# 2.net
KiCad netlist of a schematic drawn in Altium Designer
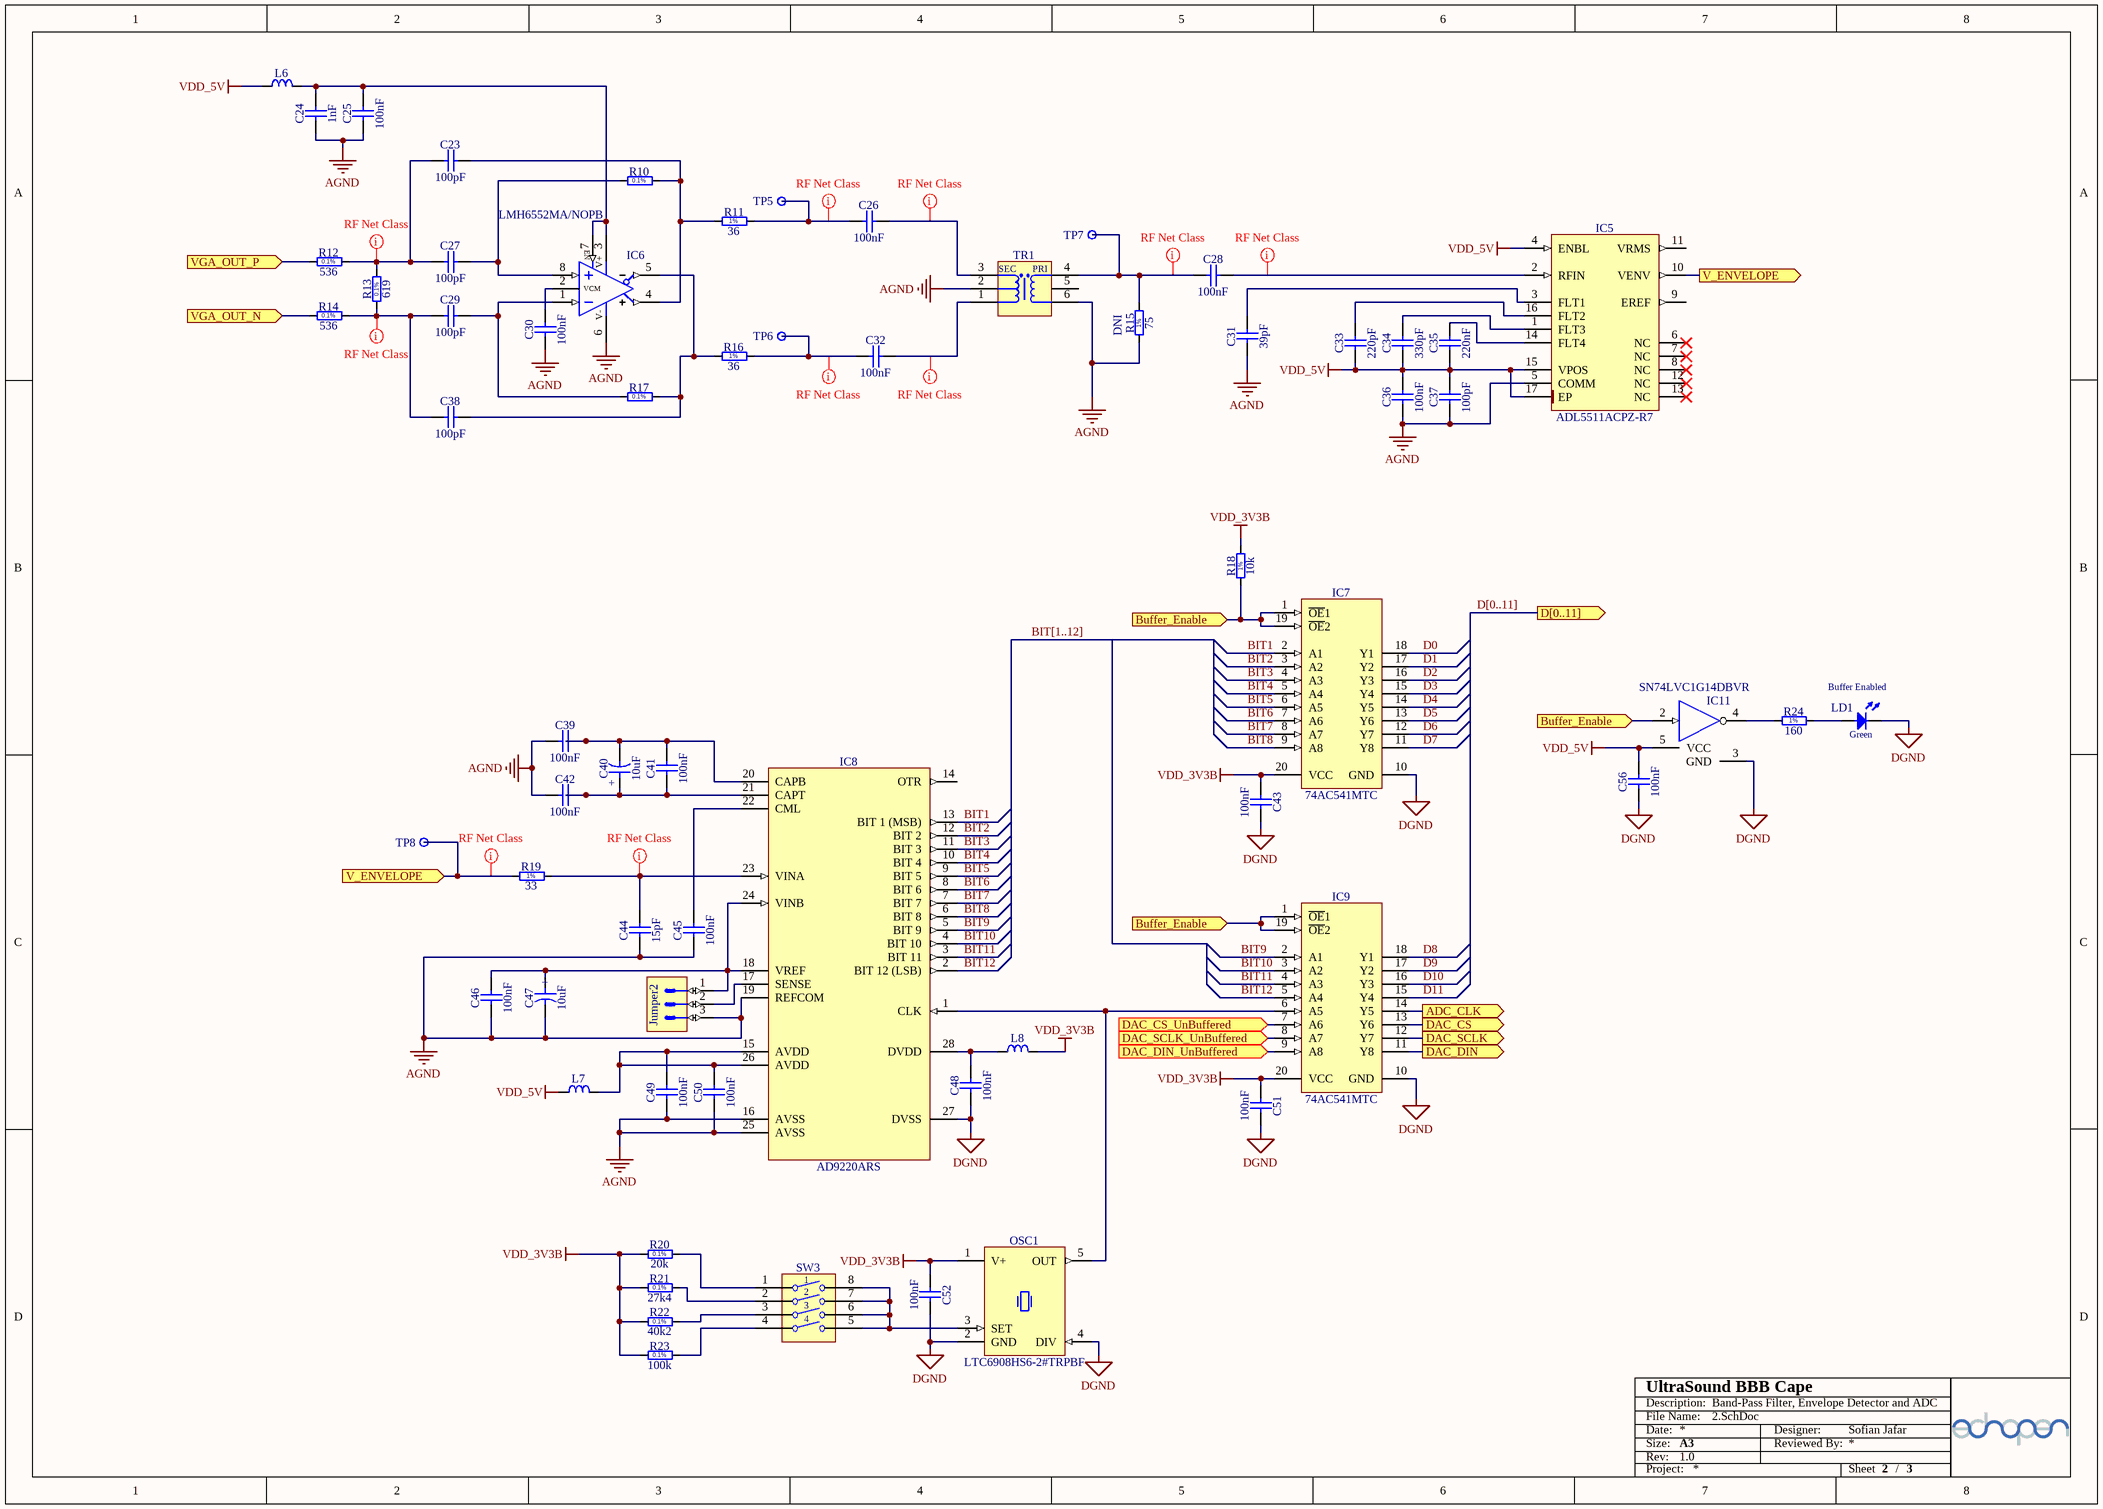
[diagram p0: 2.SchDoc]

(export (version "E")
  (design (tool "Eeschema 10.0.6"))
  (components
    (comp (ref "C23")
      (value "100pF")
      (footprint "CAPC1608X87N")
      (description "Non-polarised capacitor")
      (fields
        (field (name "PART NUMBER") "CC0603_100PF_50V_5%_NP0")
        (field (name "VOLTAGE") "50V")
        (field (name "AUTHOR") "CERN DEM JLC")
      )
      (libsource (lib "Sof-Capacitors") (part "Capacitor - non polarized"))
    )
    (comp (ref "C24")
      (value "1nF")
      (footprint "CAPC1608X87N")
      (description "Non-polarised capacitor")
      (fields
        (field (name "PART NUMBER") "CC0603_1NF_50V_10%_X7R")
        (field (name "VOLTAGE") "50V")
        (field (name "AUTHOR") "CERN DEM JLC")
      )
      (libsource (lib "Sof-Capacitors") (part "Capacitor - non polarized"))
    )
    (comp (ref "C25")
      (value "100nF")
      (footprint "CAPC1608X87N")
      (description "Non-polarised capacitor")
      (fields
        (field (name "PART NUMBER") "CC0603_100NF_50V_10%_X7R")
        (field (name "VOLTAGE") "50V")
        (field (name "AUTHOR") "CERN DEM JLC")
      )
      (libsource (lib "Sof-Capacitors") (part "Capacitor - non polarized"))
    )
    (comp (ref "C26")
      (value "100nF")
      (footprint "CAPC1608X87N")
      (description "Non-polarised capacitor")
      (fields
        (field (name "PART NUMBER") "CC0603_100NF_50V_10%_X7R")
        (field (name "VOLTAGE") "50V")
        (field (name "AUTHOR") "CERN DEM JLC")
      )
      (libsource (lib "Sof-Capacitors") (part "Capacitor - non polarized"))
    )
    (comp (ref "C27")
      (value "100pF")
      (footprint "CAPC1608X87N")
      (description "Non-polarised capacitor")
      (fields
        (field (name "PART NUMBER") "CC0603_100PF_50V_5%_NP0")
        (field (name "VOLTAGE") "50V")
        (field (name "AUTHOR") "CERN DEM JLC")
      )
      (libsource (lib "Sof-Capacitors") (part "Capacitor - non polarized"))
    )
    (comp (ref "C28")
      (value "100nF")
      (footprint "CAPC1608X87N")
      (description "Non-polarised capacitor")
      (fields
        (field (name "PART NUMBER") "CC0603_100NF_50V_10%_X7R")
        (field (name "VOLTAGE") "50V")
        (field (name "AUTHOR") "CERN DEM JLC")
      )
      (libsource (lib "Sof-Capacitors") (part "Capacitor - non polarized"))
    )
    (comp (ref "C29")
      (value "100pF")
      (footprint "CAPC1608X87N")
      (description "Non-polarised capacitor")
      (fields
        (field (name "PART NUMBER") "CC0603_100PF_50V_5%_NP0")
        (field (name "VOLTAGE") "50V")
        (field (name "AUTHOR") "CERN DEM JLC")
      )
      (libsource (lib "Sof-Capacitors") (part "Capacitor - non polarized"))
    )
    (comp (ref "C30")
      (value "100nF")
      (footprint "CAPC1608X87N")
      (description "Non-polarised capacitor")
      (fields
        (field (name "PART NUMBER") "CC0603_100NF_50V_10%_X7R")
        (field (name "VOLTAGE") "50V")
        (field (name "AUTHOR") "CERN DEM JLC")
      )
      (libsource (lib "Sof-Capacitors") (part "Capacitor - non polarized"))
    )
    (comp (ref "C31")
      (value "39pF")
      (footprint "CAPC1608X87N")
      (description "Non-polarised capacitor")
      (fields
        (field (name "PART NUMBER") "CC0603_39PF_50V_5%_NP0")
        (field (name "VOLTAGE") "50V")
        (field (name "AUTHOR") "CERN DEM JLC")
      )
      (libsource (lib "Sof-Capacitors") (part "Capacitor - non polarized"))
    )
    (comp (ref "C32")
      (value "100nF")
      (footprint "CAPC1608X87N")
      (description "Non-polarised capacitor")
      (fields
        (field (name "PART NUMBER") "CC0603_100NF_50V_10%_X7R")
        (field (name "VOLTAGE") "50V")
        (field (name "AUTHOR") "CERN DEM JLC")
      )
      (libsource (lib "Sof-Capacitors") (part "Capacitor - non polarized"))
    )
    (comp (ref "C33")
      (value "220pF")
      (footprint "CAPC1608X87N")
      (description "Non-polarised capacitor")
      (fields
        (field (name "PART NUMBER") "CC0603_220PF_50V_5%_NP0")
        (field (name "VOLTAGE") "50V")
        (field (name "AUTHOR") "CERN DEM JLC")
      )
      (libsource (lib "Sof-Capacitors") (part "Capacitor - non polarized"))
    )
    (comp (ref "C34")
      (value "330pF")
      (footprint "CAPC1608X87N")
      (description "Non-polarised capacitor")
      (fields
        (field (name "PART NUMBER") "CC0603_330PF_50V_5%_NP0")
        (field (name "VOLTAGE") "50V")
        (field (name "AUTHOR") "CERN DEM JLC")
      )
      (libsource (lib "Sof-Capacitors") (part "Capacitor - non polarized"))
    )
    (comp (ref "C35")
      (value "220nF")
      (footprint "CAPC1608X87N")
      (description "Non-polarised capacitor")
      (fields
        (field (name "PART NUMBER") "CC0603_220NF_10V_10%_X7R")
        (field (name "VOLTAGE") "10V")
        (field (name "AUTHOR") "CERN DEM JLC")
      )
      (libsource (lib "Sof-Capacitors") (part "Capacitor - non polarized"))
    )
    (comp (ref "C36")
      (value "100nF")
      (footprint "CAPC1608X87N")
      (description "Non-polarised capacitor")
      (fields
        (field (name "PART NUMBER") "CC0603_100NF_50V_10%_X7R")
        (field (name "VOLTAGE") "50V")
        (field (name "AUTHOR") "CERN DEM JLC")
      )
      (libsource (lib "Sof-Capacitors") (part "Capacitor - non polarized"))
    )
    (comp (ref "C37")
      (value "100pF")
      (footprint "CAPC1608X87N")
      (description "Non-polarised capacitor")
      (fields
        (field (name "PART NUMBER") "CC0603_100PF_50V_5%_NP0")
        (field (name "VOLTAGE") "50V")
        (field (name "AUTHOR") "CERN DEM JLC")
      )
      (libsource (lib "Sof-Capacitors") (part "Capacitor - non polarized"))
    )
    (comp (ref "C38")
      (value "100pF")
      (footprint "CAPC1608X87N")
      (description "Non-polarised capacitor")
      (fields
        (field (name "PART NUMBER") "CC0603_100PF_50V_5%_NP0")
        (field (name "VOLTAGE") "50V")
        (field (name "AUTHOR") "CERN DEM JLC")
      )
      (libsource (lib "Sof-Capacitors") (part "Capacitor - non polarized"))
    )
    (comp (ref "C39")
      (value "100nF")
      (footprint "CAPC1608X87N")
      (description "Non-polarised capacitor")
      (fields
        (field (name "PART NUMBER") "CC0603_100NF_50V_10%_X7R")
        (field (name "VOLTAGE") "50V")
        (field (name "AUTHOR") "CERN DEM JLC")
      )
      (libsource (lib "Sof-Capacitors") (part "Capacitor - non polarized"))
    )
    (comp (ref "C40")
      (value "10uF")
      (footprint "CAPMP3528X210N")
      (description "Polarised capacitor")
      (fields
        (field (name "PART NUMBER") "CTE3528-21_10UF_16V_20%_SANYO_TQC")
        (field (name "VOLTAGE") "16V")
        (field (name "AUTHOR") "CERN DEM JLC")
      )
      (libsource (lib "") (part "Capacitor - polarized_1"))
    )
    (comp (ref "C41")
      (value "100nF")
      (footprint "CAPC1608X87N")
      (description "Non-polarised capacitor")
      (fields
        (field (name "PART NUMBER") "CC0603_100NF_50V_10%_X7R")
        (field (name "VOLTAGE") "50V")
        (field (name "AUTHOR") "CERN DEM JLC")
      )
      (libsource (lib "Sof-Capacitors") (part "Capacitor - non polarized"))
    )
    (comp (ref "C42")
      (value "100nF")
      (footprint "CAPC1608X87N")
      (description "Non-polarised capacitor")
      (fields
        (field (name "PART NUMBER") "CC0603_100NF_50V_10%_X7R")
        (field (name "VOLTAGE") "50V")
        (field (name "AUTHOR") "CERN DEM JLC")
      )
      (libsource (lib "Sof-Capacitors") (part "Capacitor - non polarized"))
    )
    (comp (ref "C43")
      (value "100nF")
      (footprint "CAPC1608X87N")
      (description "Non-polarised capacitor")
      (fields
        (field (name "PART NUMBER") "CC0603_100NF_50V_10%_X7R")
        (field (name "VOLTAGE") "50V")
        (field (name "AUTHOR") "CERN DEM JLC")
      )
      (libsource (lib "Sof-Capacitors") (part "Capacitor - non polarized"))
    )
    (comp (ref "C44")
      (value "15pF")
      (footprint "CAPC1608X87N")
      (description "Non-polarised capacitor")
      (fields
        (field (name "PART NUMBER") "CC0603_15PF_50V_5%_NP0")
        (field (name "VOLTAGE") "50V")
        (field (name "AUTHOR") "CERN DEM JLC")
      )
      (libsource (lib "Sof-Capacitors") (part "Capacitor - non polarized"))
    )
    (comp (ref "C45")
      (value "100nF")
      (footprint "CAPC1608X87N")
      (description "Non-polarised capacitor")
      (fields
        (field (name "PART NUMBER") "CC0603_100NF_50V_10%_X7R")
        (field (name "VOLTAGE") "50V")
        (field (name "AUTHOR") "CERN DEM JLC")
      )
      (libsource (lib "Sof-Capacitors") (part "Capacitor - non polarized"))
    )
    (comp (ref "C46")
      (value "100nF")
      (footprint "CAPC1608X87N")
      (description "Non-polarised capacitor")
      (fields
        (field (name "PART NUMBER") "CC0603_100NF_50V_10%_X7R")
        (field (name "VOLTAGE") "50V")
        (field (name "AUTHOR") "CERN DEM JLC")
      )
      (libsource (lib "Sof-Capacitors") (part "Capacitor - non polarized"))
    )
    (comp (ref "C47")
      (value "10uF")
      (footprint "CAPMP3528X210N")
      (description "Polarised capacitor")
      (fields
        (field (name "PART NUMBER") "CTE3528-21_10UF_16V_20%_SANYO_TQC")
        (field (name "VOLTAGE") "16V")
        (field (name "AUTHOR") "CERN DEM JLC")
      )
      (libsource (lib "Sof-Capacitors") (part "Capacitor - polarized"))
    )
    (comp (ref "C48")
      (value "100nF")
      (footprint "CAPC1608X87N")
      (description "Non-polarised capacitor")
      (fields
        (field (name "PART NUMBER") "CC0603_100NF_50V_10%_X7R")
        (field (name "VOLTAGE") "50V")
        (field (name "AUTHOR") "CERN DEM JLC")
      )
      (libsource (lib "Sof-Capacitors") (part "Capacitor - non polarized"))
    )
    (comp (ref "C49")
      (value "100nF")
      (footprint "CAPC1608X87N")
      (description "Non-polarised capacitor")
      (fields
        (field (name "PART NUMBER") "CC0603_100NF_50V_10%_X7R")
        (field (name "VOLTAGE") "50V")
        (field (name "AUTHOR") "CERN DEM JLC")
      )
      (libsource (lib "Sof-Capacitors") (part "Capacitor - non polarized"))
    )
    (comp (ref "C50")
      (value "100nF")
      (footprint "CAPC1608X87N")
      (description "Non-polarised capacitor")
      (fields
        (field (name "PART NUMBER") "CC0603_100NF_50V_10%_X7R")
        (field (name "VOLTAGE") "50V")
        (field (name "AUTHOR") "CERN DEM JLC")
      )
      (libsource (lib "Sof-Capacitors") (part "Capacitor - non polarized"))
    )
    (comp (ref "C51")
      (value "100nF")
      (footprint "CAPC1608X87N")
      (description "Non-polarised capacitor")
      (fields
        (field (name "PART NUMBER") "CC0603_100NF_50V_10%_X7R")
        (field (name "VOLTAGE") "50V")
        (field (name "AUTHOR") "CERN DEM JLC")
      )
      (libsource (lib "Sof-Capacitors") (part "Capacitor - non polarized"))
    )
    (comp (ref "C52")
      (value "100nF")
      (footprint "CAPC1608X87N")
      (description "Non-polarised capacitor")
      (fields
        (field (name "PART NUMBER") "CC0603_100NF_50V_10%_X7R")
        (field (name "VOLTAGE") "50V")
        (field (name "AUTHOR") "CERN DEM JLC")
      )
      (libsource (lib "Sof-Capacitors") (part "Capacitor - non polarized"))
    )
    (comp (ref "C56")
      (value "100nF")
      (footprint "CAPC1608X87N")
      (description "Non-polarised capacitor")
      (fields
        (field (name "PART NUMBER") "CC0603_100NF_50V_10%_X7R")
        (field (name "VOLTAGE") "50V")
        (field (name "AUTHOR") "CERN DEM JLC")
      )
      (libsource (lib "Sof-Capacitors") (part "Capacitor - non polarized"))
    )
    (comp (ref "IC5")
      (value "ADL5511ACPZ-R7")
      (footprint "QFN50P300X300X80-17N-S175")
      (description "DC to 6 GHz Envelope and TruPwr RMS Detector")
      (fields (field (name "MANUFACTURER") "ANALOG DEVICES") (field (name "AUTHOR") "CERN DEM JLC"))
      (libsource (lib "Sof-ICs And Semiconductors") (part "ADL5511"))
    )
    (comp (ref "IC6")
      (value "LMH6552MA/NOPB")
      (footprint "SOIC127P600X175-8N")
      (description "1.5 GHz Fully Differential Amplifier")
      (fields (field (name "MANUFACTURER") "TEXAS INSTRUMENTS") (field (name "AUTHOR") "CERN DEM JLC"))
      (libsource (lib "Sof-ICs And Semiconductors") (part "LMH6552MA"))
    )
    (comp (ref "IC7")
      (value "74AC541MTC")
      (footprint "SOP65P640X120-20N")
      (description "Octal Buffer/Line Driver with 3-State Outputs")
      (fields (field (name "MANUFACTURER") "FAIRCHILD") (field (name "AUTHOR") "CERN DEM JLC"))
      (libsource (lib "Sof-ICs And Semiconductors") (part "74541"))
    )
    (comp (ref "IC8")
      (value "AD9220ARS")
      (footprint "SOP65P780X200-28N")
      (description "12-Bit, 10MSPS Sampling Analog-To-Digital Converter")
      (fields (field (name "MANUFACTURER") "ANALOG DEVICES") (field (name "AUTHOR") "S. Jafar"))
      (libsource (lib "Sof-ICs And Semiconductors") (part "AD9220"))
    )
    (comp (ref "IC9")
      (value "74AC541MTC")
      (footprint "SOP65P640X120-20N")
      (description "Octal Buffer/Line Driver with 3-State Outputs")
      (fields (field (name "MANUFACTURER") "FAIRCHILD") (field (name "AUTHOR") "CERN DEM JLC"))
      (libsource (lib "Sof-ICs And Semiconductors") (part "74541"))
    )
    (comp (ref "IC11")
      (value "SN74LVC1G14DBVR")
      (footprint "SOT95P280X145-5N")
      (description "Single Schmitt-Trigger Inverter")
      (fields (field (name "MANUFACTURER") "TEXAS INSTRUMENTS") (field (name "AUTHOR") "CERN DEM JLC"))
      (libsource (lib "Sof-ICs And Semiconductors") (part "741G14"))
    )
    (comp (ref "Jumper2")
      (value "~")
      (footprint "SULLINS_GRPB031VWVN")
      (description "Connector 3 Male")
      (fields
        (field (name "PART NUMBER") "SULLINS_GRPB031VWVN")
        (field (name "MANUFACTURER") "SULLINS")
        (field (name "AUTHOR") "S. Jafar")
      )
      (libsource (lib "Sof-Connectors") (part "Connector 3 Male"))
    )
    (comp (ref "L6")
      (value "75R@100MHz")
      (footprint "INDC2012X105N")
      (description "Inductor")
      (fields
        (field (name "PART NUMBER") "IND0805_MURATA_BLM21BB750SN1D")
        (field (name "POWER") "700mA")
        (field (name "AUTHOR") "S. Jafar")
      )
      (libsource (lib "Sof-Inductors & Transformers") (part "Inductor"))
    )
    (comp (ref "L7")
      (value "75R@100MHz")
      (footprint "INDC2012X105N")
      (description "Inductor")
      (fields
        (field (name "PART NUMBER") "IND0805_MURATA_BLM21BB750SN1D")
        (field (name "POWER") "700mA")
        (field (name "AUTHOR") "S. Jafar")
      )
      (libsource (lib "Sof-Inductors & Transformers") (part "Inductor"))
    )
    (comp (ref "L8")
      (value "75R@100MHz")
      (footprint "INDC2012X105N")
      (description "Inductor")
      (fields
        (field (name "PART NUMBER") "IND0805_MURATA_BLM21BB750SN1D")
        (field (name "POWER") "700mA")
        (field (name "AUTHOR") "S. Jafar")
      )
      (libsource (lib "Sof-Inductors & Transformers") (part "Inductor"))
    )
    (comp (ref "LD1")
      (value "Green")
      (footprint "LED_OSRAM_LGL29K")
      (description "LED Green 1C 2A")
      (fields
        (field (name "PART NUMBER") "LED_OSRAM_LG L29K-G2J1-24-Z")
        (field (name "MANUFACTURER") "OSRAM")
        (field (name "AUTHOR") "CERN DEM JLC")
      )
      (libsource (lib "Sof-ICs And Semiconductors") (part "LED Green 1C 2A"))
    )
    (comp (ref "OSC1")
      (value "LTC6908HS6-2#TRPBF")
      (footprint "SOT95P280X100-6N")
      (description "Resistor Set SOT-23 Oscillator 1kHz-20MHz")
      (fields
        (field (name "PART NUMBER") "LTC6900CS5")
        (field (name "MANUFACTURER") "LINEAR TECHNOLOGY")
        (field (name "AUTHOR") "S.Jafar")
      )
      (libsource (lib "Sof-ICs And Semiconductors") (part "LTC6900CS5"))
    )
    (comp (ref "R10")
      (value "1k07")
      (footprint "RESC1608X55N")
      (description "Resistor - 0.1%")
      (fields
        (field (name "PART NUMBER") "R0603_1K07_0.1%_0.063W_10PPM")
        (field (name "POWER") "0.063W")
        (field (name "AUTHOR") "CERN DEM JLC")
      )
      (libsource (lib "Sof-Resistors") (part "Resistor - 0.1%"))
    )
    (comp (ref "R11")
      (value "36")
      (footprint "RESC1608X55N")
      (description "Resistor - 1%")
      (fields
        (field (name "PART NUMBER") "R0603_36R_1%_0.1W_100PPM")
        (field (name "POWER") "0.1W")
        (field (name "AUTHOR") "CERN DEM JLC")
      )
      (libsource (lib "Sof-Resistors") (part "Resistor - 1%"))
    )
    (comp (ref "R12")
      (value "536")
      (footprint "RESC1608X55N")
      (description "Resistor - 0.1%")
      (fields
        (field (name "PART NUMBER") "R0603_536R_0.1%_0.063W_10PPM")
        (field (name "POWER") "0.063W")
        (field (name "AUTHOR") "CERN DEM JLC")
      )
      (libsource (lib "Sof-Resistors") (part "Resistor - 0.1%"))
    )
    (comp (ref "R13")
      (value "619")
      (footprint "RESC1608X55N")
      (description "Resistor - 0.1%")
      (fields
        (field (name "PART NUMBER") "R0603_619R_0.1%_0.063W_10PPM")
        (field (name "POWER") "0.063W")
        (field (name "AUTHOR") "CERN DEM JLC")
      )
      (libsource (lib "Sof-Resistors") (part "Resistor - 0.1%"))
    )
    (comp (ref "R14")
      (value "536")
      (footprint "RESC1608X55N")
      (description "Resistor - 0.1%")
      (fields
        (field (name "PART NUMBER") "R0603_536R_0.1%_0.063W_10PPM")
        (field (name "POWER") "0.063W")
        (field (name "AUTHOR") "CERN DEM JLC")
      )
      (libsource (lib "Sof-Resistors") (part "Resistor - 0.1%"))
    )
    (comp (ref "R15")
      (value "75")
      (footprint "RESC1608X55N")
      (description "Resistor - 1%")
      (fields
        (field (name "PART NUMBER") "R0603_75R_1%_0.1W_100PPM")
        (field (name "POWER") "0.1W")
        (field (name "MOUNTED") "DNI")
        (field (name "AUTHOR") "CERN DEM JLC")
      )
      (libsource (lib "Sof-Resistors") (part "Resistor - 1%"))
    )
    (comp (ref "R16")
      (value "36")
      (footprint "RESC1608X55N")
      (description "Resistor - 1%")
      (fields
        (field (name "PART NUMBER") "R0603_36R_1%_0.1W_100PPM")
        (field (name "POWER") "0.1W")
        (field (name "AUTHOR") "CERN DEM JLC")
      )
      (libsource (lib "Sof-Resistors") (part "Resistor - 1%"))
    )
    (comp (ref "R17")
      (value "1k07")
      (footprint "RESC1608X55N")
      (description "Resistor - 0.1%")
      (fields
        (field (name "PART NUMBER") "R0603_1K07_0.1%_0.063W_10PPM")
        (field (name "POWER") "0.063W")
        (field (name "AUTHOR") "CERN DEM JLC")
      )
      (libsource (lib "Sof-Resistors") (part "Resistor - 0.1%"))
    )
    (comp (ref "R18")
      (value "10k")
      (footprint "RESC1608X55N")
      (description "Resistor - 1%")
      (fields
        (field (name "PART NUMBER") "R0603_10K_1%_0.1W_100PPM")
        (field (name "POWER") "0.1W")
        (field (name "AUTHOR") "CERN DEM JLC")
      )
      (libsource (lib "Sof-Resistors") (part "Resistor - 1%"))
    )
    (comp (ref "R19")
      (value "33")
      (footprint "RESC1608X55N")
      (description "Resistor - 1%")
      (fields
        (field (name "PART NUMBER") "R0603_33R_1%_0.1W_100PPM")
        (field (name "POWER") "0.1W")
        (field (name "AUTHOR") "CERN DEM JLC")
      )
      (libsource (lib "Sof-Resistors") (part "Resistor - 1%"))
    )
    (comp (ref "R20")
      (value "20k")
      (footprint "RESC1608X55N")
      (description "Resistor - 0.1%")
      (fields
        (field (name "PART NUMBER") "R0603_20K_0.1%_0.063W_10PPM")
        (field (name "POWER") "0.063W")
        (field (name "AUTHOR") "CERN DEM JLC")
      )
      (libsource (lib "Sof-Resistors") (part "Resistor - 0.1%"))
    )
    (comp (ref "R21")
      (value "27k4")
      (footprint "RESC1608X55N")
      (description "Resistor - 0.1%")
      (fields
        (field (name "PART NUMBER") "R0603_27K4_0.1%_0.063W_10PPM")
        (field (name "POWER") "0.063W")
        (field (name "AUTHOR") "CERN DEM JLC")
      )
      (libsource (lib "Sof-Resistors") (part "Resistor - 0.1%"))
    )
    (comp (ref "R22")
      (value "40k2")
      (footprint "RESC1608X55N")
      (description "Resistor - 0.1%")
      (fields
        (field (name "PART NUMBER") "R0603_40K2_0.1%_0.063W_10PPM")
        (field (name "POWER") "0.063W")
        (field (name "AUTHOR") "CERN DEM JLC")
      )
      (libsource (lib "Sof-Resistors") (part "Resistor - 0.1%"))
    )
    (comp (ref "R23")
      (value "100k")
      (footprint "RESC1608X55N")
      (description "Resistor - 0.1%")
      (fields
        (field (name "PART NUMBER") "R0603_100K_0.1%_0.063W_10PPM")
        (field (name "POWER") "0.063W")
        (field (name "AUTHOR") "CERN DEM JLC")
      )
      (libsource (lib "Sof-Resistors") (part "Resistor - 0.1%"))
    )
    (comp (ref "R24")
      (value "160")
      (footprint "RESC1608X55N")
      (description "Resistor - 1%")
      (fields
        (field (name "PART NUMBER") "R0603_160R_1%_0.1W_100PPM")
        (field (name "POWER") "0.1W")
        (field (name "AUTHOR") "CERN DEM JLC")
      )
      (libsource (lib "Sof-Resistors") (part "Resistor - 1%"))
    )
    (comp (ref "SW3")
      (value "Switch")
      (footprint "SW_TYCO_1571983-4")
      (description "4 Ways SPST DIP Switch")
      (fields
        (field (name "PART NUMBER") "SW_TYCO_1571983-4")
        (field (name "MANUFACTURER") "TYCO")
        (field (name "AUTHOR") "CERN DEM JLC")
      )
      (libsource (lib "Sof-Eletro-mechanical") (part "SW 4x SPST DIP Switch"))
    )
    (comp (ref "TP5")
      (value "Test Point")
      (footprint "NICOMATIC_C12000B")
      (fields
        (field (name "PART NUMBER") "NICOMATIC_C12000B")
        (field (name "MANUFACTURER") "NICOMATIC")
        (field (name "MANUFACTURER PART NUMBER") "C12000B")
        (field (name "AUTHOR") "CERN DEM JLC")
      )
      (libsource (lib "Sof-Connectors") (part "Test Point"))
    )
    (comp (ref "TP6")
      (value "Test Point")
      (footprint "NICOMATIC_C12000B")
      (fields
        (field (name "PART NUMBER") "NICOMATIC_C12000B")
        (field (name "MANUFACTURER") "NICOMATIC")
        (field (name "MANUFACTURER PART NUMBER") "C12000B")
        (field (name "AUTHOR") "CERN DEM JLC")
      )
      (libsource (lib "Sof-Connectors") (part "Test Point"))
    )
    (comp (ref "TP7")
      (value "Test Point")
      (footprint "NICOMATIC_C12000B")
      (fields
        (field (name "PART NUMBER") "NICOMATIC_C12000B")
        (field (name "MANUFACTURER") "NICOMATIC")
        (field (name "MANUFACTURER PART NUMBER") "C12000B")
        (field (name "AUTHOR") "CERN DEM JLC")
      )
      (libsource (lib "Sof-Connectors") (part "Test Point"))
    )
    (comp (ref "TP8")
      (value "Test Point")
      (footprint "NICOMATIC_C12000B")
      (fields
        (field (name "PART NUMBER") "NICOMATIC_C12000B")
        (field (name "MANUFACTURER") "NICOMATIC")
        (field (name "MANUFACTURER PART NUMBER") "C12000B")
        (field (name "AUTHOR") "CERN DEM JLC")
      )
      (libsource (lib "Sof-Connectors") (part "Test Point"))
    )
    (comp (ref "TR1")
      (value "1:1")
      (footprint "XFMR_MINI-CIRCUITS_KK81")
      (description "50 Ohm 0.015 To 300MHz RF Transformers")
      (fields
        (field (name "PART NUMBER") "XFMR_MINI-CIRCUITS_T1-6T-KK81")
        (field (name "MANUFACTURER") "MINI-CIRCUITS")
        (field (name "AUTHOR") "S. Jafar")
      )
      (libsource (lib "Sof-Inductors & Transformers") (part "XFMR_MINI-CIRCUITS_T1-6T-KK81"))
    )
  )
  (nets
    (net (code "1") (name "/ADC_CLK") (class "Default")
      (node (ref "IC9") (pin "14") (pinfunction "Y5_14") (pintype "tri_state"))
    )
    (net (code "2") (name "/BIT1") (class "Default")
      (node (ref "IC7") (pin "2") (pinfunction "A1_2") (pintype "input"))
      (node (ref "IC8") (pin "13") (pinfunction "BIT_1_(MSB)_13") (pintype "output"))
    )
    (net (code "3") (name "/BIT2") (class "Default")
      (node (ref "IC7") (pin "3") (pinfunction "A2_3") (pintype "input"))
      (node (ref "IC8") (pin "12") (pinfunction "BIT_2_12") (pintype "output"))
    )
    (net (code "4") (name "/BIT3") (class "Default")
      (node (ref "IC7") (pin "4") (pinfunction "A3_4") (pintype "input"))
      (node (ref "IC8") (pin "11") (pinfunction "BIT_3_11") (pintype "output"))
    )
    (net (code "5") (name "/BIT4") (class "Default")
      (node (ref "IC7") (pin "5") (pinfunction "A4_5") (pintype "input"))
      (node (ref "IC8") (pin "10") (pinfunction "BIT_4_10") (pintype "output"))
    )
    (net (code "6") (name "/BIT5") (class "Default")
      (node (ref "IC7") (pin "6") (pinfunction "A5_6") (pintype "input"))
      (node (ref "IC8") (pin "9") (pinfunction "BIT_5_9") (pintype "output"))
    )
    (net (code "7") (name "/BIT6") (class "Default")
      (node (ref "IC7") (pin "7") (pinfunction "A6_7") (pintype "input"))
      (node (ref "IC8") (pin "8") (pinfunction "BIT_6_8") (pintype "output"))
    )
    (net (code "8") (name "/BIT7") (class "Default")
      (node (ref "IC7") (pin "8") (pinfunction "A7_8") (pintype "input"))
      (node (ref "IC8") (pin "7") (pinfunction "BIT_7_7") (pintype "output"))
    )
    (net (code "9") (name "/BIT8") (class "Default")
      (node (ref "IC7") (pin "9") (pinfunction "A8_9") (pintype "input"))
      (node (ref "IC8") (pin "6") (pinfunction "BIT_8_6") (pintype "output"))
    )
    (net (code "10") (name "/BIT9") (class "Default")
      (node (ref "IC8") (pin "5") (pinfunction "BIT_9_5") (pintype "output"))
      (node (ref "IC9") (pin "2") (pinfunction "A1_2") (pintype "input"))
    )
    (net (code "11") (name "/BIT10") (class "Default")
      (node (ref "IC8") (pin "4") (pinfunction "BIT_10_4") (pintype "output"))
      (node (ref "IC9") (pin "3") (pinfunction "A2_3") (pintype "input"))
    )
    (net (code "12") (name "/BIT11") (class "Default")
      (node (ref "IC8") (pin "3") (pinfunction "BIT_11_3") (pintype "output"))
      (node (ref "IC9") (pin "4") (pinfunction "A3_4") (pintype "input"))
    )
    (net (code "13") (name "/BIT12") (class "Default")
      (node (ref "IC8") (pin "2") (pinfunction "BIT_12_(LSB)_2") (pintype "output"))
      (node (ref "IC9") (pin "5") (pinfunction "A4_5") (pintype "input"))
    )
    (net (code "15") (name "/Buffer_Enable") (class "Default")
      (node (ref "IC11") (pin "2") (pinfunction "IN_2") (pintype "input"))
      (node (ref "IC7") (pin "1") (pinfunction "~{OE}1_1") (pintype "input"))
      (node (ref "IC7") (pin "19") (pinfunction "~{OE}2_19") (pintype "input"))
      (node (ref "IC9") (pin "1") (pinfunction "~{OE}1_1") (pintype "input"))
      (node (ref "IC9") (pin "19") (pinfunction "~{OE}2_19") (pintype "input"))
      (node (ref "R18") (pin "1") (pinfunction "1_1") (pintype "passive"))
    )
    (net (code "16") (name "/D0") (class "Default")
      (node (ref "IC7") (pin "18") (pinfunction "Y1_18") (pintype "tri_state"))
    )
    (net (code "17") (name "/D1") (class "Default")
      (node (ref "IC7") (pin "17") (pinfunction "Y2_17") (pintype "tri_state"))
    )
    (net (code "18") (name "/D2") (class "Default")
      (node (ref "IC7") (pin "16") (pinfunction "Y3_16") (pintype "tri_state"))
    )
    (net (code "19") (name "/D3") (class "Default")
      (node (ref "IC7") (pin "15") (pinfunction "Y4_15") (pintype "tri_state"))
    )
    (net (code "20") (name "/D4") (class "Default")
      (node (ref "IC7") (pin "14") (pinfunction "Y5_14") (pintype "tri_state"))
    )
    (net (code "21") (name "/D5") (class "Default")
      (node (ref "IC7") (pin "13") (pinfunction "Y6_13") (pintype "tri_state"))
    )
    (net (code "22") (name "/D6") (class "Default")
      (node (ref "IC7") (pin "12") (pinfunction "Y7_12") (pintype "tri_state"))
    )
    (net (code "23") (name "/D7") (class "Default")
      (node (ref "IC7") (pin "11") (pinfunction "Y8_11") (pintype "tri_state"))
    )
    (net (code "24") (name "/D8") (class "Default")
      (node (ref "IC9") (pin "18") (pinfunction "Y1_18") (pintype "tri_state"))
    )
    (net (code "25") (name "/D9") (class "Default")
      (node (ref "IC9") (pin "17") (pinfunction "Y2_17") (pintype "tri_state"))
    )
    (net (code "26") (name "/D10") (class "Default")
      (node (ref "IC9") (pin "16") (pinfunction "Y3_16") (pintype "tri_state"))
    )
    (net (code "27") (name "/D11") (class "Default")
      (node (ref "IC9") (pin "15") (pinfunction "Y4_15") (pintype "tri_state"))
    )
    (net (code "28") (name "/DAC_CS") (class "Default")
      (node (ref "IC9") (pin "13") (pinfunction "Y6_13") (pintype "tri_state"))
    )
    (net (code "29") (name "/DAC_CS_UnBuffered") (class "Default")
      (node (ref "IC9") (pin "7") (pinfunction "A6_7") (pintype "input"))
    )
    (net (code "30") (name "/DAC_DIN") (class "Default")
      (node (ref "IC9") (pin "11") (pinfunction "Y8_11") (pintype "tri_state"))
    )
    (net (code "31") (name "/DAC_DIN_UnBuffered") (class "Default")
      (node (ref "IC9") (pin "9") (pinfunction "A8_9") (pintype "input"))
    )
    (net (code "32") (name "/DAC_SCLK") (class "Default")
      (node (ref "IC9") (pin "12") (pinfunction "Y7_12") (pintype "tri_state"))
    )
    (net (code "33") (name "/DAC_SCLK_UnBuffered") (class "Default")
      (node (ref "IC9") (pin "8") (pinfunction "A7_8") (pintype "input"))
    )
    (net (code "35") (name "/VGA_OUT_N") (class "Default")
      (node (ref "R14") (pin "1") (pinfunction "1_1") (pintype "passive"))
    )
    (net (code "36") (name "/VGA_OUT_P") (class "Default")
      (node (ref "R12") (pin "1") (pinfunction "1_1") (pintype "passive"))
    )
    (net (code "37") (name "/V_ENVELOPE") (class "Default")
      (node (ref "IC5") (pin "10") (pinfunction "VENV_10") (pintype "output"))
      (node (ref "R19") (pin "1") (pinfunction "1_1") (pintype "passive"))
      (node (ref "TP8") (pin "1") (pinfunction "1_1") (pintype "bidirectional"))
    )
    (net (code "38") (name "AGND") (class "Default")
      (node (ref "C24") (pin "1") (pinfunction "1_1") (pintype "passive"))
      (node (ref "C25") (pin "2") (pinfunction "2_2") (pintype "passive"))
      (node (ref "C30") (pin "2") (pinfunction "2_2") (pintype "passive"))
      (node (ref "C31") (pin "1") (pinfunction "1_1") (pintype "passive"))
      (node (ref "C36") (pin "1") (pinfunction "1_1") (pintype "passive"))
      (node (ref "C37") (pin "1") (pinfunction "1_1") (pintype "passive"))
      (node (ref "C39") (pin "1") (pinfunction "1_1") (pintype "passive"))
      (node (ref "C42") (pin "1") (pinfunction "1_1") (pintype "passive"))
      (node (ref "C44") (pin "1") (pinfunction "1_1") (pintype "passive"))
      (node (ref "C45") (pin "2") (pinfunction "2_2") (pintype "passive"))
      (node (ref "C46") (pin "1") (pinfunction "1_1") (pintype "passive"))
      (node (ref "C47") (pin "2") (pinfunction "2_2") (pintype "passive"))
      (node (ref "C49") (pin "1") (pinfunction "1_1") (pintype "passive"))
      (node (ref "C50") (pin "1") (pinfunction "1_1") (pintype "passive"))
      (node (ref "IC5") (pin "5") (pinfunction "COMM_5") (pintype "power_in"))
      (node (ref "IC6") (pin "6") (pinfunction "V-_6") (pintype "power_in"))
      (node (ref "IC8") (pin "16") (pinfunction "AVSS_16") (pintype "passive"))
      (node (ref "IC8") (pin "19") (pinfunction "REFCOM_19") (pintype "power_in"))
      (node (ref "IC8") (pin "25") (pinfunction "AVSS_25") (pintype "passive"))
      (node (ref "Jumper2") (pin "3") (pinfunction "3_3") (pintype "bidirectional"))
      (node (ref "R15") (pin "1") (pinfunction "1_1") (pintype "passive"))
      (node (ref "TR1") (pin "2") (pinfunction "NC_2") (pintype "passive"))
      (node (ref "TR1") (pin "6") (pinfunction "S_6") (pintype "passive"))
    )
    (net (code "39") (name "DGND") (class "Default")
      (node (ref "C43") (pin "1") (pinfunction "1_1") (pintype "passive"))
      (node (ref "C48") (pin "1") (pinfunction "1_1") (pintype "passive"))
      (node (ref "C51") (pin "1") (pinfunction "1_1") (pintype "passive"))
      (node (ref "C52") (pin "1") (pinfunction "1_1") (pintype "passive"))
      (node (ref "C56") (pin "2") (pinfunction "2_2") (pintype "passive"))
      (node (ref "IC11") (pin "3") (pinfunction "GND_3") (pintype "power_in"))
      (node (ref "IC7") (pin "10") (pinfunction "GND_10") (pintype "power_in"))
      (node (ref "IC8") (pin "27") (pinfunction "DVSS_27") (pintype "power_in"))
      (node (ref "IC9") (pin "10") (pinfunction "GND_10") (pintype "power_in"))
      (node (ref "LD1") (pin "1") (pinfunction "C_1") (pintype "passive"))
      (node (ref "OSC1") (pin "2") (pinfunction "GND_2") (pintype "power_in"))
      (node (ref "OSC1") (pin "4") (pinfunction "DIV_4") (pintype "input"))
    )
    (net (code "40") (name "Net-(C23-Pad1)") (class "Default")
      (node (ref "C23") (pin "1") (pinfunction "1_1") (pintype "passive"))
      (node (ref "C27") (pin "1") (pinfunction "1_1") (pintype "passive"))
      (node (ref "R12") (pin "2") (pinfunction "2_2") (pintype "passive"))
      (node (ref "R13") (pin "2") (pinfunction "2_2") (pintype "passive"))
    )
    (net (code "41") (name "Net-(C26-Pad2)") (class "Default")
      (node (ref "C26") (pin "2") (pinfunction "2_2") (pintype "passive"))
      (node (ref "R11") (pin "2") (pinfunction "2_2") (pintype "passive"))
      (node (ref "TP5") (pin "1") (pinfunction "1_1") (pintype "bidirectional"))
    )
    (net (code "42") (name "Net-(C29-Pad1)") (class "Default")
      (node (ref "C29") (pin "1") (pinfunction "1_1") (pintype "passive"))
      (node (ref "C38") (pin "1") (pinfunction "1_1") (pintype "passive"))
      (node (ref "R13") (pin "1") (pinfunction "1_1") (pintype "passive"))
      (node (ref "R14") (pin "2") (pinfunction "2_2") (pintype "passive"))
    )
    (net (code "43") (name "Net-(C32-Pad2)") (class "Default")
      (node (ref "C32") (pin "2") (pinfunction "2_2") (pintype "passive"))
      (node (ref "R16") (pin "2") (pinfunction "2_2") (pintype "passive"))
      (node (ref "TP6") (pin "1") (pinfunction "1_1") (pintype "bidirectional"))
    )
    (net (code "44") (name "Net-(C49-Pad2)") (class "Default")
      (node (ref "C49") (pin "2") (pinfunction "2_2") (pintype "passive"))
      (node (ref "C50") (pin "2") (pinfunction "2_2") (pintype "passive"))
      (node (ref "IC8") (pin "15") (pinfunction "AVDD_15") (pintype "passive"))
      (node (ref "IC8") (pin "26") (pinfunction "AVDD_26") (pintype "passive"))
      (node (ref "L7") (pin "2") (pinfunction "2_2") (pintype "passive"))
    )
    (net (code "45") (name "Net-(IC5-FLT1)") (class "Default")
      (node (ref "C31") (pin "2") (pinfunction "2_2") (pintype "passive"))
      (node (ref "IC5") (pin "3") (pinfunction "FLT1_3") (pintype "passive"))
    )
    (net (code "46") (name "Net-(IC5-FLT2)") (class "Default")
      (node (ref "C33") (pin "2") (pinfunction "2_2") (pintype "passive"))
      (node (ref "IC5") (pin "16") (pinfunction "FLT2_16") (pintype "passive"))
    )
    (net (code "47") (name "Net-(IC5-FLT3)") (class "Default")
      (node (ref "C34") (pin "2") (pinfunction "2_2") (pintype "passive"))
      (node (ref "IC5") (pin "1") (pinfunction "FLT3_1") (pintype "passive"))
    )
    (net (code "48") (name "Net-(IC5-FLT4)") (class "Default")
      (node (ref "C35") (pin "2") (pinfunction "2_2") (pintype "passive"))
      (node (ref "IC5") (pin "14") (pinfunction "FLT4_14") (pintype "passive"))
    )
    (net (code "49") (name "Net-(IC5-RFIN)") (class "Default")
      (node (ref "C28") (pin "2") (pinfunction "2_2") (pintype "passive"))
      (node (ref "IC5") (pin "2") (pinfunction "RFIN_2") (pintype "input"))
    )
    (net (code "50") (name "Net-(IC6-EN)") (class "Default")
      (node (ref "C24") (pin "2") (pinfunction "2_2") (pintype "passive"))
      (node (ref "C25") (pin "1") (pinfunction "1_1") (pintype "passive"))
      (node (ref "IC6") (pin "3") (pinfunction "V+_3") (pintype "power_in"))
      (node (ref "IC6") (pin "7") (pinfunction "EN_7") (pintype "input"))
      (node (ref "L6") (pin "2") (pinfunction "2_2") (pintype "passive"))
    )
    (net (code "51") (name "Net-(IC6-IN+)") (class "Default")
      (node (ref "C27") (pin "2") (pinfunction "2_2") (pintype "passive"))
      (node (ref "IC6") (pin "8") (pinfunction "IN+_8") (pintype "input"))
      (node (ref "R10") (pin "1") (pinfunction "1_1") (pintype "passive"))
    )
    (net (code "52") (name "Net-(IC6-IN-)") (class "Default")
      (node (ref "C29") (pin "2") (pinfunction "2_2") (pintype "passive"))
      (node (ref "IC6") (pin "1") (pinfunction "IN-_1") (pintype "input"))
      (node (ref "R17") (pin "1") (pinfunction "1_1") (pintype "passive"))
    )
    (net (code "53") (name "Net-(IC6-VOCM)") (class "Default")
      (node (ref "C30") (pin "1") (pinfunction "1_1") (pintype "passive"))
      (node (ref "IC6") (pin "2") (pinfunction "VOCM_2") (pintype "passive"))
    )
    (net (code "54") (name "Net-(IC6-VOUT+)") (class "Default")
      (node (ref "C23") (pin "2") (pinfunction "2_2") (pintype "passive"))
      (node (ref "IC6") (pin "4") (pinfunction "VOUT+_4") (pintype "output"))
      (node (ref "R10") (pin "2") (pinfunction "2_2") (pintype "passive"))
      (node (ref "R11") (pin "1") (pinfunction "1_1") (pintype "passive"))
    )
    (net (code "55") (name "Net-(IC6-VOUT-)") (class "Default")
      (node (ref "C38") (pin "2") (pinfunction "2_2") (pintype "passive"))
      (node (ref "IC6") (pin "5") (pinfunction "VOUT-_5") (pintype "output"))
      (node (ref "R16") (pin "1") (pinfunction "1_1") (pintype "passive"))
      (node (ref "R17") (pin "2") (pinfunction "2_2") (pintype "passive"))
    )
    (net (code "56") (name "Net-(IC8-CAPB)") (class "Default")
      (node (ref "C39") (pin "2") (pinfunction "2_2") (pintype "passive"))
      (node (ref "C40") (pin "2") (pinfunction "2_2") (pintype "passive"))
      (node (ref "C41") (pin "2") (pinfunction "2_2") (pintype "passive"))
      (node (ref "IC8") (pin "20") (pinfunction "CAPB_20") (pintype "passive"))
    )
    (net (code "57") (name "Net-(IC8-CAPT)") (class "Default")
      (node (ref "C40") (pin "1") (pinfunction "1_1") (pintype "passive"))
      (node (ref "C41") (pin "1") (pinfunction "1_1") (pintype "passive"))
      (node (ref "C42") (pin "2") (pinfunction "2_2") (pintype "passive"))
      (node (ref "IC8") (pin "21") (pinfunction "CAPT_21") (pintype "passive"))
    )
    (net (code "58") (name "Net-(IC8-CLK)") (class "Default")
      (node (ref "IC8") (pin "1") (pinfunction "CLK_1") (pintype "input"))
      (node (ref "IC9") (pin "6") (pinfunction "A5_6") (pintype "input"))
      (node (ref "OSC1") (pin "5") (pinfunction "OUT_5") (pintype "output"))
    )
    (net (code "59") (name "Net-(IC8-CML)") (class "Default")
      (node (ref "C45") (pin "1") (pinfunction "1_1") (pintype "passive"))
      (node (ref "IC8") (pin "22") (pinfunction "CML_22") (pintype "passive"))
    )
    (net (code "60") (name "Net-(IC8-DVDD)") (class "Default")
      (node (ref "C48") (pin "2") (pinfunction "2_2") (pintype "passive"))
      (node (ref "IC8") (pin "28") (pinfunction "DVDD_28") (pintype "power_in"))
      (node (ref "L8") (pin "1") (pinfunction "1_1") (pintype "passive"))
    )
    (net (code "61") (name "Net-(IC8-SENSE)") (class "Default")
      (node (ref "IC8") (pin "17") (pinfunction "SENSE_17") (pintype "power_in"))
      (node (ref "Jumper2") (pin "2") (pinfunction "2_2") (pintype "bidirectional"))
    )
    (net (code "62") (name "Net-(IC8-VINA)") (class "Default")
      (node (ref "C44") (pin "2") (pinfunction "2_2") (pintype "passive"))
      (node (ref "IC8") (pin "23") (pinfunction "VINA_23") (pintype "input"))
      (node (ref "R19") (pin "2") (pinfunction "2_2") (pintype "passive"))
    )
    (net (code "63") (name "Net-(IC8-VINB)") (class "Default")
      (node (ref "C46") (pin "2") (pinfunction "2_2") (pintype "passive"))
      (node (ref "C47") (pin "1") (pinfunction "1_1") (pintype "passive"))
      (node (ref "IC8") (pin "18") (pinfunction "VREF_18") (pintype "passive"))
      (node (ref "IC8") (pin "24") (pinfunction "VINB_24") (pintype "input"))
      (node (ref "Jumper2") (pin "1") (pinfunction "1_1") (pintype "bidirectional"))
    )
    (net (code "64") (name "Net-(IC11-OUT)") (class "Default")
      (node (ref "IC11") (pin "4") (pinfunction "OUT_4") (pintype "open_collector"))
      (node (ref "R24") (pin "1") (pinfunction "1_1") (pintype "passive"))
    )
    (net (code "65") (name "Net-(LD1-A)") (class "Default")
      (node (ref "LD1") (pin "2") (pinfunction "A_2") (pintype "passive"))
      (node (ref "R24") (pin "2") (pinfunction "2_2") (pintype "passive"))
    )
    (net (code "66") (name "Net-(OSC1-SET)") (class "Default")
      (node (ref "OSC1") (pin "3") (pinfunction "SET_3") (pintype "input"))
      (node (ref "SW3") (pin "5") (pinfunction "5_5") (pintype "passive"))
      (node (ref "SW3") (pin "6") (pinfunction "6_6") (pintype "passive"))
      (node (ref "SW3") (pin "7") (pinfunction "7_7") (pintype "passive"))
      (node (ref "SW3") (pin "8") (pinfunction "8_8") (pintype "passive"))
    )
    (net (code "67") (name "Net-(R20-Pad2)") (class "Default")
      (node (ref "R20") (pin "2") (pinfunction "2_2") (pintype "passive"))
      (node (ref "SW3") (pin "1") (pinfunction "1_1") (pintype "passive"))
    )
    (net (code "68") (name "Net-(R21-Pad2)") (class "Default")
      (node (ref "R21") (pin "2") (pinfunction "2_2") (pintype "passive"))
      (node (ref "SW3") (pin "2") (pinfunction "2_2") (pintype "passive"))
    )
    (net (code "69") (name "Net-(R22-Pad2)") (class "Default")
      (node (ref "R22") (pin "2") (pinfunction "2_2") (pintype "passive"))
      (node (ref "SW3") (pin "3") (pinfunction "3_3") (pintype "passive"))
    )
    (net (code "70") (name "Net-(R23-Pad2)") (class "Default")
      (node (ref "R23") (pin "2") (pinfunction "2_2") (pintype "passive"))
      (node (ref "SW3") (pin "4") (pinfunction "4_4") (pintype "passive"))
    )
    (net (code "71") (name "Net-(TR1-P)") (class "Default")
      (node (ref "C32") (pin "1") (pinfunction "1_1") (pintype "passive"))
      (node (ref "TR1") (pin "1") (pinfunction "P_1") (pintype "passive"))
    )
    (net (code "72") (name "Net-(TR1-PDOT)") (class "Default")
      (node (ref "C26") (pin "1") (pinfunction "1_1") (pintype "passive"))
      (node (ref "TR1") (pin "3") (pinfunction "PDOT_3") (pintype "passive"))
    )
    (net (code "73") (name "Net-(TR1-SDOT)") (class "Default")
      (node (ref "C28") (pin "1") (pinfunction "1_1") (pintype "passive"))
      (node (ref "R15") (pin "2") (pinfunction "2_2") (pintype "passive"))
      (node (ref "TP7") (pin "1") (pinfunction "1_1") (pintype "bidirectional"))
      (node (ref "TR1") (pin "4") (pinfunction "SDOT_4") (pintype "passive"))
    )
    (net (code "74") (name "VDD_3V3B") (class "Default")
      (node (ref "C43") (pin "2") (pinfunction "2_2") (pintype "passive"))
      (node (ref "C51") (pin "2") (pinfunction "2_2") (pintype "passive"))
      (node (ref "C52") (pin "2") (pinfunction "2_2") (pintype "passive"))
      (node (ref "IC7") (pin "20") (pinfunction "VCC_20") (pintype "power_in"))
      (node (ref "IC9") (pin "20") (pinfunction "VCC_20") (pintype "power_in"))
      (node (ref "L8") (pin "2") (pinfunction "2_2") (pintype "passive"))
      (node (ref "OSC1") (pin "1") (pinfunction "V+_1") (pintype "power_in"))
      (node (ref "R18") (pin "2") (pinfunction "2_2") (pintype "passive"))
      (node (ref "R20") (pin "1") (pinfunction "1_1") (pintype "passive"))
      (node (ref "R21") (pin "1") (pinfunction "1_1") (pintype "passive"))
      (node (ref "R22") (pin "1") (pinfunction "1_1") (pintype "passive"))
      (node (ref "R23") (pin "1") (pinfunction "1_1") (pintype "passive"))
    )
    (net (code "75") (name "VDD_5V") (class "Default")
      (node (ref "C33") (pin "1") (pinfunction "1_1") (pintype "passive"))
      (node (ref "C34") (pin "1") (pinfunction "1_1") (pintype "passive"))
      (node (ref "C35") (pin "1") (pinfunction "1_1") (pintype "passive"))
      (node (ref "C36") (pin "2") (pinfunction "2_2") (pintype "passive"))
      (node (ref "C37") (pin "2") (pinfunction "2_2") (pintype "passive"))
      (node (ref "C56") (pin "1") (pinfunction "1_1") (pintype "passive"))
      (node (ref "IC11") (pin "5") (pinfunction "VCC_5") (pintype "power_in"))
      (node (ref "IC5") (pin "15") (pinfunction "VPOS_15") (pintype "power_in"))
      (node (ref "IC5") (pin "17") (pinfunction "EP_17") (pintype "power_in"))
      (node (ref "IC5") (pin "4") (pinfunction "ENBL_4") (pintype "input"))
      (node (ref "L6") (pin "1") (pinfunction "1_1") (pintype "passive"))
      (node (ref "L7") (pin "1") (pinfunction "1_1") (pintype "passive"))
    )
    (net (code "76") (name "unconnected-(IC5-EREF-Pad9)") (class "Default")
      (node (ref "IC5") (pin "9") (pinfunction "EREF_9") (pintype "output"))
    )
    (net (code "77") (name "unconnected-(IC5-NC-Pad6)") (class "Default")
      (node (ref "IC5") (pin "6") (pinfunction "NC_6") (pintype "passive+no_connect"))
    )
    (net (code "78") (name "unconnected-(IC5-NC-Pad7)") (class "Default")
      (node (ref "IC5") (pin "7") (pinfunction "NC_7") (pintype "passive+no_connect"))
    )
    (net (code "79") (name "unconnected-(IC5-NC-Pad8)") (class "Default")
      (node (ref "IC5") (pin "8") (pinfunction "NC_8") (pintype "passive+no_connect"))
    )
    (net (code "80") (name "unconnected-(IC5-NC-Pad12)") (class "Default")
      (node (ref "IC5") (pin "12") (pinfunction "NC_12") (pintype "passive+no_connect"))
    )
    (net (code "81") (name "unconnected-(IC5-NC-Pad13)") (class "Default")
      (node (ref "IC5") (pin "13") (pinfunction "NC_13") (pintype "passive+no_connect"))
    )
    (net (code "82") (name "unconnected-(IC5-VRMS-Pad11)") (class "Default")
      (node (ref "IC5") (pin "11") (pinfunction "VRMS_11") (pintype "output"))
    )
    (net (code "83") (name "unconnected-(IC8-OTR-Pad14)") (class "Default")
      (node (ref "IC8") (pin "14") (pinfunction "OTR_14") (pintype "output"))
    )
    (net (code "84") (name "unconnected-(TR1-NC-Pad5)") (class "Default")
      (node (ref "TR1") (pin "5") (pinfunction "NC_5") (pintype "passive"))
    )
  )
)
